# TMS320F28379D_PWM.net
KiCad netlist of a schematic drawn in Altium Designer
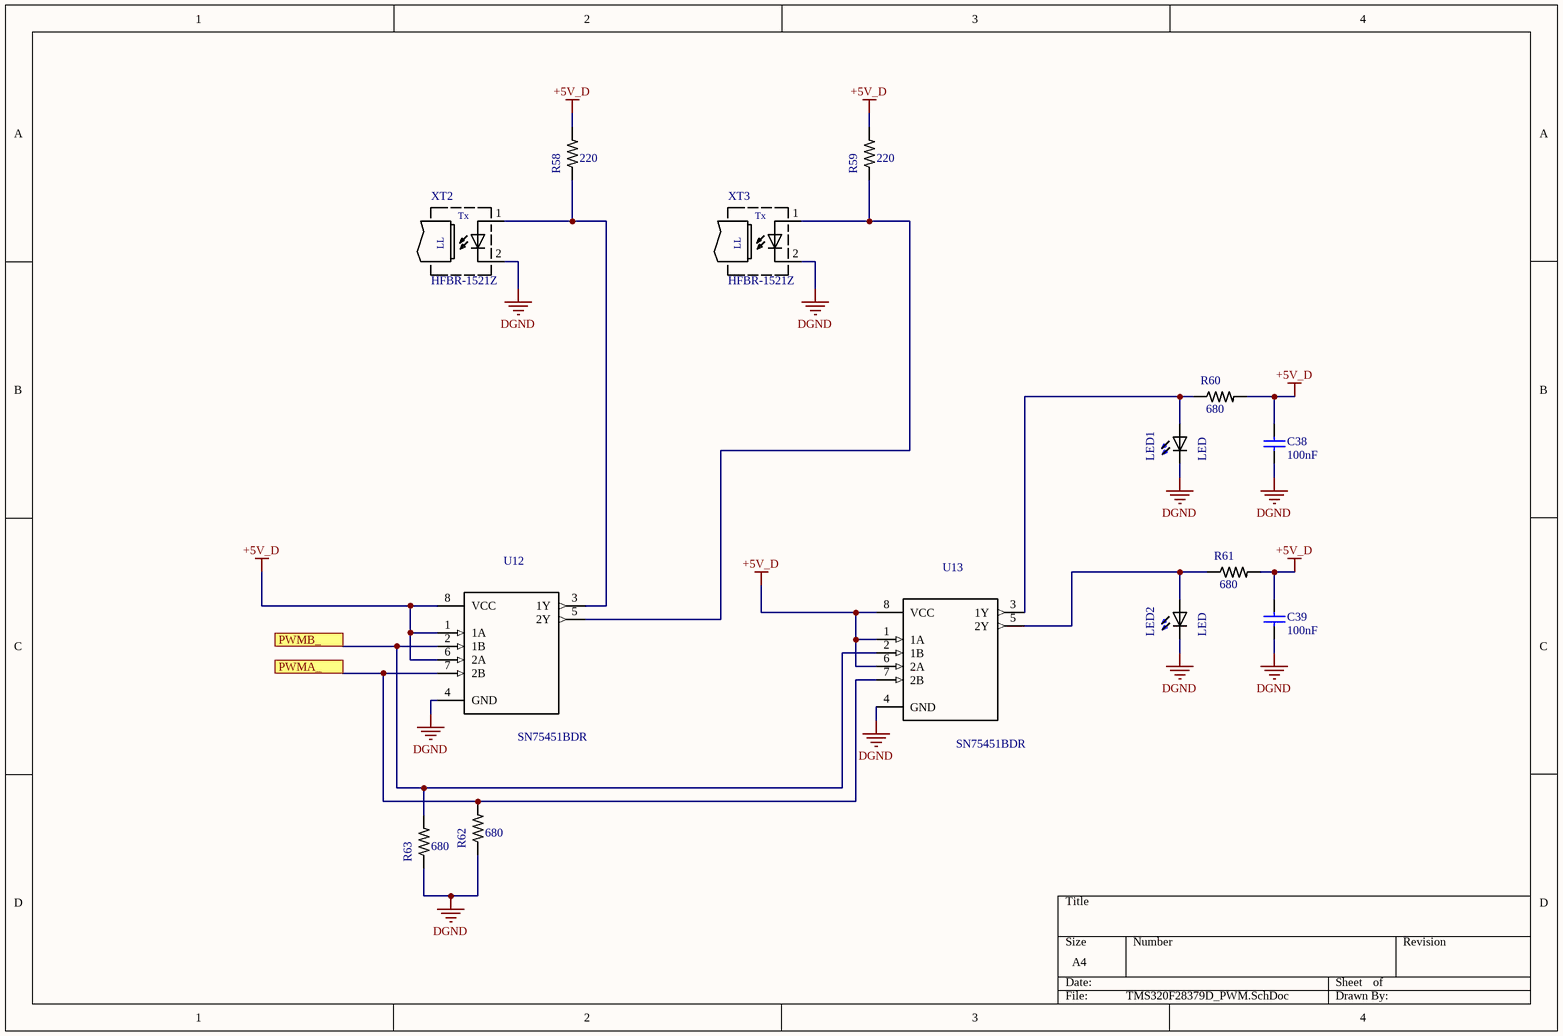
[diagram p0: TMS320F28379D_PWM.SchDoc]

(export (version "E")
  (design (tool "Eeschema 10.0.6"))
  (components
    (comp (ref "C38")
      (value "100nF")
      (footprint "CAP 0805")
      (fields (field (name "Comment") "Cap cerámico"))
      (libsource (lib "Condensadores") (part "Cap cerámico"))
    )
    (comp (ref "C39")
      (value "100nF")
      (footprint "CAP 0805")
      (fields (field (name "Comment") "Cap cerámico"))
      (libsource (lib "Condensadores") (part "Cap cerámico"))
    )
    (comp (ref "LED1")
      (value "LED")
      (footprint "LED_0805")
      (description "Led")
      (fields
        (field (name "DIGI-KEY PART NUMBER") "732-4984-1-ND")
        (field (name "MANUFACTURER PART NUMBER") "150080RS75000")
      )
      (libsource (lib "Fibras Opticas") (part "LED"))
    )
    (comp (ref "LED2")
      (value "LED")
      (footprint "LED_0805")
      (description "Led")
      (fields
        (field (name "DIGI-KEY PART NUMBER") "732-4984-1-ND")
        (field (name "MANUFACTURER PART NUMBER") "150080RS75000")
      )
      (libsource (lib "Fibras Opticas") (part "LED"))
    )
    (comp (ref "R58")
      (value "220")
      (footprint "Resistor 0805")
      (description "Resistor")
      (fields (field (name "Comment") "Resistor 0805"))
      (libsource (lib "Resistencias") (part "Resistor"))
    )
    (comp (ref "R59")
      (value "220")
      (footprint "Resistor 0805")
      (description "Resistor")
      (fields (field (name "Comment") "Resistor 0805"))
      (libsource (lib "Resistencias") (part "Resistor"))
    )
    (comp (ref "R60")
      (value "680")
      (footprint "Resistor 0805")
      (description "Resistor")
      (fields (field (name "Comment") "Resistor 0805"))
      (libsource (lib "Resistencias") (part "Resistor"))
    )
    (comp (ref "R61")
      (value "680")
      (footprint "Resistor 0805")
      (description "Resistor")
      (fields (field (name "Comment") "Resistor 0805"))
      (libsource (lib "Resistencias") (part "Resistor"))
    )
    (comp (ref "R62")
      (value "680")
      (footprint "Resistor 0805")
      (description "Resistor")
      (fields (field (name "Comment") "Resistor 0805"))
      (libsource (lib "Resistencias") (part "Resistor"))
    )
    (comp (ref "R63")
      (value "680")
      (footprint "Resistor 0805")
      (description "Resistor")
      (fields (field (name "Comment") "Resistor 0805"))
      (libsource (lib "Resistencias") (part "Resistor"))
    )
    (comp (ref "U12")
      (value "SN75451BDR")
      (footprint "8-SOIC")
      (description "Dual Very-High Speed, High-Current Peripheral Drivers 8-SOIC 0 to 70")
      (fields (field (name "DIGI-KEY PART NUMBER") "296-14960-6-ND"))
      (libsource (lib "Circuitos integrados") (part "SN75451BDR"))
    )
    (comp (ref "U13")
      (value "SN75451BDR")
      (footprint "8-SOIC")
      (description "Dual Very-High Speed, High-Current Peripheral Drivers 8-SOIC 0 to 70")
      (fields (field (name "DIGI-KEY PART NUMBER") "296-14960-6-ND"))
      (libsource (lib "Circuitos integrados") (part "SN75451BDR"))
    )
    (comp (ref "XT2")
      (value "HFBR-1521Z")
      (footprint "HFBR-15X1Z")
      (fields (field (name "DIGI-KEY PART NUMBER") "516-2043-ND"))
      (libsource (lib "Fibras Opticas") (part "HFBR-1521Z"))
    )
    (comp (ref "XT3")
      (value "HFBR-1521Z")
      (footprint "HFBR-15X1Z")
      (fields (field (name "DIGI-KEY PART NUMBER") "516-2043-ND"))
      (libsource (lib "Fibras Opticas") (part "HFBR-1521Z"))
    )
  )
  (nets
    (net (code "1") (name "+5V_D") (class "Default")
      (node (ref "C38") (pin "1") (pinfunction "1_1") (pintype "passive"))
      (node (ref "C39") (pin "1") (pinfunction "1_1") (pintype "passive"))
      (node (ref "R58") (pin "2") (pinfunction "2_2") (pintype "passive"))
      (node (ref "R59") (pin "2") (pinfunction "2_2") (pintype "passive"))
      (node (ref "R60") (pin "2") (pinfunction "2_2") (pintype "passive"))
      (node (ref "R61") (pin "2") (pinfunction "2_2") (pintype "passive"))
      (node (ref "U12") (pin "1") (pinfunction "1A_1") (pintype "input"))
      (node (ref "U12") (pin "6") (pinfunction "2A_6") (pintype "input"))
      (node (ref "U12") (pin "8") (pinfunction "VCC_8") (pintype "power_in"))
      (node (ref "U13") (pin "1") (pinfunction "1A_1") (pintype "input"))
      (node (ref "U13") (pin "6") (pinfunction "2A_6") (pintype "input"))
      (node (ref "U13") (pin "8") (pinfunction "VCC_8") (pintype "power_in"))
    )
    (net (code "2") (name "/PWMA_") (class "Default")
      (node (ref "R62") (pin "2") (pinfunction "2_2") (pintype "passive"))
      (node (ref "U12") (pin "7") (pinfunction "2B_7") (pintype "input"))
      (node (ref "U13") (pin "7") (pinfunction "2B_7") (pintype "input"))
    )
    (net (code "3") (name "/PWMB_") (class "Default")
      (node (ref "R63") (pin "2") (pinfunction "2_2") (pintype "passive"))
      (node (ref "U12") (pin "2") (pinfunction "1B_2") (pintype "input"))
      (node (ref "U13") (pin "2") (pinfunction "1B_2") (pintype "input"))
    )
    (net (code "4") (name "DGND") (class "Default")
      (node (ref "C38") (pin "2") (pinfunction "2_2") (pintype "passive"))
      (node (ref "C39") (pin "2") (pinfunction "2_2") (pintype "passive"))
      (node (ref "LED1") (pin "1") (pinfunction "NEG_1") (pintype "passive"))
      (node (ref "LED2") (pin "1") (pinfunction "NEG_1") (pintype "passive"))
      (node (ref "R62") (pin "1") (pinfunction "1_1") (pintype "passive"))
      (node (ref "R63") (pin "1") (pinfunction "1_1") (pintype "passive"))
      (node (ref "U12") (pin "4") (pinfunction "GND_4") (pintype "passive"))
      (node (ref "U13") (pin "4") (pinfunction "GND_4") (pintype "passive"))
      (node (ref "XT2") (pin "2") (pinfunction "C_2") (pintype "passive"))
      (node (ref "XT3") (pin "2") (pinfunction "C_2") (pintype "passive"))
    )
    (net (code "5") (name "Net-(LED1-POS)") (class "Default")
      (node (ref "LED1") (pin "2") (pinfunction "POS_2") (pintype "passive"))
      (node (ref "R60") (pin "1") (pinfunction "1_1") (pintype "passive"))
      (node (ref "U13") (pin "3") (pinfunction "1Y_3") (pintype "output"))
    )
    (net (code "6") (name "Net-(LED2-POS)") (class "Default")
      (node (ref "LED2") (pin "2") (pinfunction "POS_2") (pintype "passive"))
      (node (ref "R61") (pin "1") (pinfunction "1_1") (pintype "passive"))
      (node (ref "U13") (pin "5") (pinfunction "2Y_5") (pintype "output"))
    )
    (net (code "7") (name "Net-(U12-1Y)") (class "Default")
      (node (ref "R58") (pin "1") (pinfunction "1_1") (pintype "passive"))
      (node (ref "U12") (pin "3") (pinfunction "1Y_3") (pintype "output"))
      (node (ref "XT2") (pin "1") (pinfunction "A_1") (pintype "passive"))
    )
    (net (code "8") (name "Net-(U12-2Y)") (class "Default")
      (node (ref "R59") (pin "1") (pinfunction "1_1") (pintype "passive"))
      (node (ref "U12") (pin "5") (pinfunction "2Y_5") (pintype "output"))
      (node (ref "XT3") (pin "1") (pinfunction "A_1") (pintype "passive"))
    )
  )
)
